# Charger.net
KiCad netlist of a schematic drawn in Altium Designer
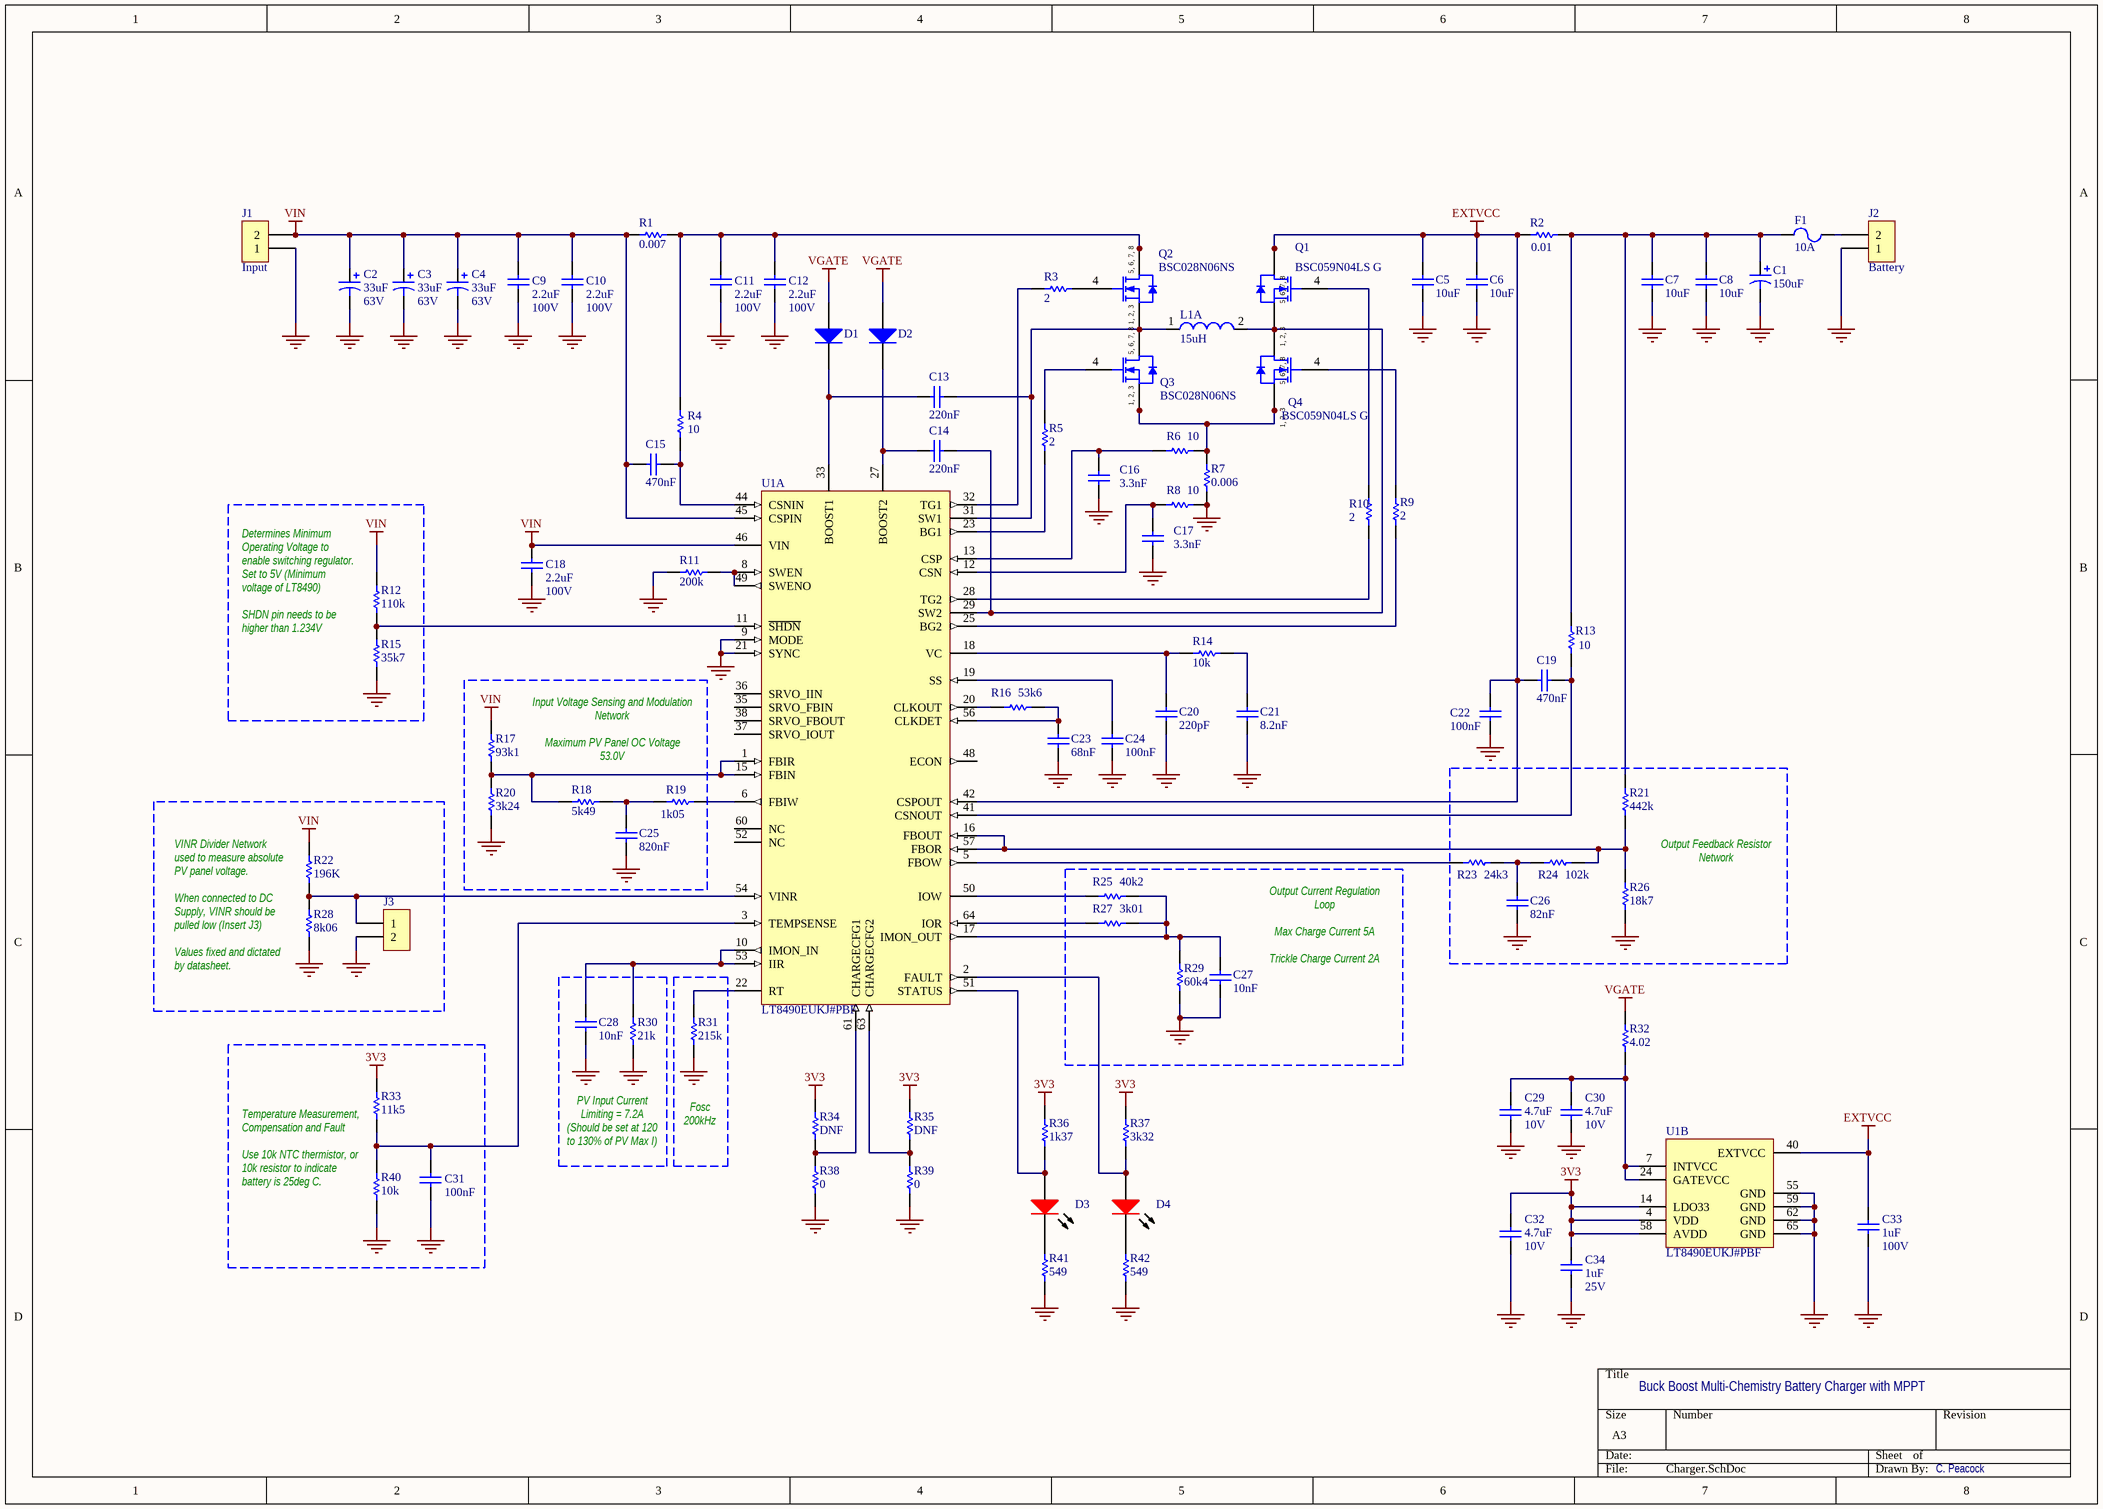
[diagram p0: Charger.SchDoc]

(export (version "E")
  (design (tool "Eeschema 10.0.6"))
  (components
    (comp (ref "C1")
      (value "150uF")
      (footprint "PCB-h7n8m0mive84y4pjomrj-1")
      (description "Capacitor Alum Elec, 150uf, 20%, 50v, Capacitor Alum Elec, 150uf, 20%, 50v, Smd, Full Reel")
      (libsource (lib "CommunityVault") (part "CMP-38bcf3ec736fe77b-2"))
    )
    (comp (ref "C2")
      (value "33uF")
      (footprint "PCB-9g04u1co75526zy4kkrl-1")
      (description "Cap Aluminum Lytic 33uF 63V 20% (8 X 10.2mm) SMD 250mA 2000h 105C Automotive T/R")
      (fields
        (field (name "MANUFACTURER PART NUMBER") "EEEFK1J330P")
        (field (name "VOLTAGE RATING (DC)") "63V")
      )
      (libsource (lib "CommunityVault") (part "CMP-7693bfcb6deba954-1"))
    )
    (comp (ref "C3")
      (value "33uF")
      (footprint "PCB-9g04u1co75526zy4kkrl-1")
      (description "Cap Aluminum Lytic 33uF 63V 20% (8 X 10.2mm) SMD 250mA 2000h 105C Automotive T/R")
      (fields
        (field (name "MANUFACTURER PART NUMBER") "EEEFK1J330P")
        (field (name "VOLTAGE RATING (DC)") "63V")
      )
      (libsource (lib "CommunityVault") (part "CMP-7693bfcb6deba954-1"))
    )
    (comp (ref "C4")
      (value "33uF")
      (footprint "PCB-9g04u1co75526zy4kkrl-1")
      (description "Cap Aluminum Lytic 33uF 63V 20% (8 X 10.2mm) SMD 250mA 2000h 105C Automotive T/R")
      (fields
        (field (name "MANUFACTURER PART NUMBER") "EEEFK1J330P")
        (field (name "VOLTAGE RATING (DC)") "63V")
      )
      (libsource (lib "CommunityVault") (part "CMP-7693bfcb6deba954-1"))
    )
    (comp (ref "C5")
      (value "10uF")
      (footprint "PCB-41pvis4jpu9wge287x0a-1")
      (description "1210 10 uF 35 V ±10% Tolerance X7R SMT Multilayer Ceramic Capacitor")
      (fields (field (name "MANUFACTURER PART NUMBER") "GRM32ER7YA106KA12L"))
      (libsource (lib "CommunityVault") (part "CMP-bd5774f6f82f6290-1"))
    )
    (comp (ref "C6")
      (value "10uF")
      (footprint "PCB-41pvis4jpu9wge287x0a-1")
      (description "1210 10 uF 35 V ±10% Tolerance X7R SMT Multilayer Ceramic Capacitor")
      (fields (field (name "MANUFACTURER PART NUMBER") "GRM32ER7YA106KA12L"))
      (libsource (lib "CommunityVault") (part "CMP-bd5774f6f82f6290-1"))
    )
    (comp (ref "C7")
      (value "10uF")
      (footprint "PCB-41pvis4jpu9wge287x0a-1")
      (description "1210 10 uF 35 V ±10% Tolerance X7R SMT Multilayer Ceramic Capacitor")
      (fields (field (name "MANUFACTURER PART NUMBER") "GRM32ER7YA106KA12L"))
      (libsource (lib "CommunityVault") (part "CMP-bd5774f6f82f6290-1"))
    )
    (comp (ref "C8")
      (value "10uF")
      (footprint "PCB-41pvis4jpu9wge287x0a-1")
      (description "1210 10 uF 35 V ±10% Tolerance X7R SMT Multilayer Ceramic Capacitor")
      (fields (field (name "MANUFACTURER PART NUMBER") "GRM32ER7YA106KA12L"))
      (libsource (lib "CommunityVault") (part "CMP-bd5774f6f82f6290-1"))
    )
    (comp (ref "C9")
      (value "2.2uF")
      (footprint "CAPC3225X279X50NL20T25")
      (description "Cap Ceramic 2.2uF 100V X7R 10% SMD 1210 125C Embossed T/R")
      (fields
        (field (name "VOLTAGE RATING (DC)") "100V")
        (field (name "MANUFACTURER PART NUMBER") "12101C225KAT2A")
      )
      (libsource (lib "CommunityVault") (part "CMP-2511202-3"))
    )
    (comp (ref "C10")
      (value "2.2uF")
      (footprint "CAPC3225X279X50NL20T25")
      (description "Cap Ceramic 2.2uF 100V X7R 10% SMD 1210 125C Embossed T/R")
      (fields
        (field (name "VOLTAGE RATING (DC)") "100V")
        (field (name "MANUFACTURER PART NUMBER") "12101C225KAT2A")
      )
      (libsource (lib "CommunityVault") (part "CMP-2511202-3"))
    )
    (comp (ref "C11")
      (value "2.2uF")
      (footprint "CAPC3225X279X50NL20T25")
      (description "Cap Ceramic 2.2uF 100V X7R 10% SMD 1210 125C Embossed T/R")
      (fields
        (field (name "VOLTAGE RATING (DC)") "100V")
        (field (name "MANUFACTURER PART NUMBER") "12101C225KAT2A")
      )
      (libsource (lib "CommunityVault") (part "CMP-2511202-3"))
    )
    (comp (ref "C12")
      (value "2.2uF")
      (footprint "CAPC3225X279X50NL20T25")
      (description "Cap Ceramic 2.2uF 100V X7R 10% SMD 1210 125C Embossed T/R")
      (fields
        (field (name "VOLTAGE RATING (DC)") "100V")
        (field (name "MANUFACTURER PART NUMBER") "12101C225KAT2A")
      )
      (libsource (lib "CommunityVault") (part "CMP-2511202-3"))
    )
    (comp (ref "C13")
      (value "220nF")
      (footprint "CAPC2013X140X50ML20T25")
      (description "Multilayer Ceramic Capacitors MLCC - SMD/SMT 50volts .22uF 5% X7R 7inch reel")
      (fields (field (name "MANUFACTURER PART NUMBER") "08055C224JAT2A"))
      (libsource (lib "CommunityVault") (part "CMP-3551434-3"))
    )
    (comp (ref "C14")
      (value "220nF")
      (footprint "CAPC2013X140X50ML20T25")
      (description "Multilayer Ceramic Capacitors MLCC - SMD/SMT 50volts .22uF 5% X7R 7inch reel")
      (fields (field (name "MANUFACTURER PART NUMBER") "08055C224JAT2A"))
      (libsource (lib "CommunityVault") (part "CMP-3551434-3"))
    )
    (comp (ref "C15")
      (value "470nF")
      (footprint "CAPC2013X140X50ML20T25")
      (description "Multilayer Ceramic Capacitors MLCC - SMD/SMT .47uF 50v 20% Tol.")
      (fields (field (name "MANUFACTURER PART NUMBER") "08055C474JAT2A"))
      (libsource (lib "CommunityVault") (part "CMP-3555014-4"))
    )
    (comp (ref "C16")
      (value "3.3nF")
      (footprint "CAPC2013X94X50ML20T25")
      (description "CAP CER 3300PF 50V 5% X7R 0805")
      (fields (field (name "MANUFACTURER PART NUMBER") "08055C332JAT2A"))
      (libsource (lib "CommunityVault") (part "CMP-173641-3"))
    )
    (comp (ref "C17")
      (value "3.3nF")
      (footprint "CAPC2013X94X50ML20T25")
      (description "CAP CER 3300PF 50V 5% X7R 0805")
      (fields (field (name "MANUFACTURER PART NUMBER") "08055C332JAT2A"))
      (libsource (lib "CommunityVault") (part "CMP-173641-3"))
    )
    (comp (ref "C18")
      (value "2.2uF")
      (footprint "CAPC3225X279X50NL20T25")
      (description "Cap Ceramic 2.2uF 100V X7R 10% SMD 1210 125C Embossed T/R")
      (fields
        (field (name "VOLTAGE RATING (DC)") "100V")
        (field (name "MANUFACTURER PART NUMBER") "12101C225KAT2A")
      )
      (libsource (lib "CommunityVault") (part "CMP-2511202-3"))
    )
    (comp (ref "C19")
      (value "470nF")
      (footprint "CAPC2013X140X50ML20T25")
      (description "Multilayer Ceramic Capacitors MLCC - SMD/SMT .47uF 50v 20% Tol.")
      (fields (field (name "MANUFACTURER PART NUMBER") "08055C474JAT2A"))
      (libsource (lib "CommunityVault") (part "CMP-3555014-4"))
    )
    (comp (ref "C20")
      (value "220pF")
      (footprint "CAPC2013X94X50ML20T25")
      (description "CAP CER 220PF 50V 5% X7R 0805")
      (fields (field (name "MANUFACTURER PART NUMBER") "08055C221JAT2A"))
      (libsource (lib "CommunityVault") (part "CMP-173636-3"))
    )
    (comp (ref "C21")
      (value "8.2nF")
      (footprint "CAPC2013X94X50ML20T25")
      (description "CAP CER 8200PF 50V 5% X7R 0805")
      (fields (field (name "MANUFACTURER PART NUMBER") "08055C822JAT2A"))
      (libsource (lib "CommunityVault") (part "CMP-173647-3"))
    )
    (comp (ref "C22")
      (value "100nF")
      (footprint "CAPC2013X140X50ML20T25")
      (description "Capacitor; Ceramic; Cap 0.1 uF; Tol 5%; Vol-Rtg 50 VDC; SMT; 0805; X7R; Tape & Reel")
      (fields (field (name "MANUFACTURER PART NUMBER") "08055C104JAT2A"))
      (libsource (lib "CommunityVault") (part "CMP-54a29ee556ae8b65-2"))
    )
    (comp (ref "C23")
      (value "68nF")
      (footprint "CAPC2013X94X50ML20T25")
      (description "CAP CER 0.068UF 50V 5% X7R 0805")
      (fields (field (name "MANUFACTURER PART NUMBER") "08055C683JAT2A"))
      (libsource (lib "CommunityVault") (part "CMP-174430-3"))
    )
    (comp (ref "C24")
      (value "100nF")
      (footprint "CAPC2013X140X50ML20T25")
      (description "Capacitor; Ceramic; Cap 0.1 uF; Tol 5%; Vol-Rtg 50 VDC; SMT; 0805; X7R; Tape & Reel")
      (fields (field (name "MANUFACTURER PART NUMBER") "08055C104JAT2A"))
      (libsource (lib "CommunityVault") (part "CMP-54a29ee556ae8b65-2"))
    )
    (comp (ref "C25")
      (value "820nF")
      (footprint "CAPC2013X95X45NL10T25")
      (description "Multilayer Ceramic Capacitors MLCC - SMD/SMT 0.82uF 25Volts X7R 0.1")
      (fields (field (name "MANUFACTURER PART NUMBER") "GRM219R71E824KA88D"))
      (libsource (lib "CommunityVault") (part "CAP-2"))
    )
    (comp (ref "C26")
      (value "82nF")
      (footprint "CAPC2013X94X50ML20T25")
      (description "CAP CER 0.082UF 50V 5% X7R 0805")
      (fields (field (name "MANUFACTURER PART NUMBER") "08055C823JAT2A"))
      (libsource (lib "CommunityVault") (part "CMP-174432-3"))
    )
    (comp (ref "C27")
      (value "10nF")
      (footprint "CAPC2013X94X50ML20T25")
      (description "cap smd 0805")
      (fields (field (name "MANUFACTURER PART NUMBER") "08055C103JAT2A"))
      (libsource (lib "CommunityVault") (part "CMP-16466678-4"))
    )
    (comp (ref "C28")
      (value "10nF")
      (footprint "CAPC2013X94X50ML20T25")
      (description "CAP CER 10NF 50V 5% X7R 0805")
      (fields (field (name "MANUFACTURER PART NUMBER") "08055C103JAT2A"))
      (libsource (lib "CommunityVault") (part "CMP-16466678-5"))
    )
    (comp (ref "C29")
      (value "4.7uF")
      (footprint "CAPC2013X140X50ML20T25")
      (description "CAP CER 4.7UF 10V 10% X5R 0805")
      (fields
        (field (name "VOLTAGE RATING (DC)") "10V")
        (field (name "MANUFACTURER PART NUMBER") "0805ZD475KAT2A")
      )
      (libsource (lib "CommunityVault") (part "CMP-126761-3"))
    )
    (comp (ref "C30")
      (value "4.7uF")
      (footprint "CAPC2013X140X50ML20T25")
      (description "CAP CER 4.7UF 10V 10% X5R 0805")
      (fields
        (field (name "VOLTAGE RATING (DC)") "10V")
        (field (name "MANUFACTURER PART NUMBER") "0805ZD475KAT2A")
      )
      (libsource (lib "CommunityVault") (part "CMP-126761-3"))
    )
    (comp (ref "C31")
      (value "100nF")
      (footprint "CAPC2013X140X50ML20T25")
      (description "Capacitor; Ceramic; Cap 0.1 uF; Tol 5%; Vol-Rtg 50 VDC; SMT; 0805; X7R; Tape & Reel")
      (fields (field (name "MANUFACTURER PART NUMBER") "08055C104JAT2A"))
      (libsource (lib "CommunityVault") (part "CMP-54a29ee556ae8b65-2"))
    )
    (comp (ref "C32")
      (value "4.7uF")
      (footprint "CAPC2013X140X50ML20T25")
      (description "CAP CER 4.7UF 10V 10% X5R 0805")
      (fields
        (field (name "VOLTAGE RATING (DC)") "10V")
        (field (name "MANUFACTURER PART NUMBER") "0805ZD475KAT2A")
      )
      (libsource (lib "CommunityVault") (part "CMP-126761-3"))
    )
    (comp (ref "C33")
      (value "1uF")
      (footprint "CAPC3225X279X50ML20T25")
      (description "CAP CER 1UF 100V 10% X7R 1210")
      (fields
        (field (name "VOLTAGE RATING (DC)") "100V")
        (field (name "MANUFACTURER PART NUMBER") "12101C105KAT2A")
      )
      (libsource (lib "CommunityVault") (part "CMP-127163-3"))
    )
    (comp (ref "C34")
      (value "1uF")
      (footprint "CAPC2013X140X50ML20T25")
      (description "CAP CER 1UF 25V 10% X5R 0805")
      (fields
        (field (name "MANUFACTURER PART NUMBER") "08053D105KAT2A")
        (field (name "VOLTAGE RATING (DC)") "25V")
      )
      (libsource (lib "CommunityVault") (part "CAP-2"))
    )
    (comp (ref "D1")
      (value "1N4148WS")
      (footprint "FSC-1N4148WS-SOD-323-2")
      (description "DIODE GEN PURP 75V 150MA SOD323F")
      (libsource (lib "CommunityVault") (part "D_K1A2-2"))
    )
    (comp (ref "D2")
      (value "1N4148WS")
      (footprint "FSC-1N4148WS-SOD-323-2")
      (description "DIODE GEN PURP 75V 150MA SOD323F")
      (libsource (lib "CommunityVault") (part "D_K1A2-2"))
    )
    (comp (ref "D3")
      (value "Lite-On LTST-C170KRKT")
      (footprint "PCB-5ta9mte2am12bu12jwvi-1")
      (description "Red 2 x 1.25 x 1.1 mm 130° Water Clear 54 mcd 2 V LED Surface Mount")
      (fields (field (name "MANUFACTURER PART NUMBER") "LTST-C170KRKT"))
      (libsource (lib "CommunityVault") (part "CMP-1544870-4"))
    )
    (comp (ref "D4")
      (value "Lite-On LTST-C170KRKT")
      (footprint "PCB-5ta9mte2am12bu12jwvi-1")
      (description "Red 2 x 1.25 x 1.1 mm 130° Water Clear 54 mcd 2 V LED Surface Mount")
      (fields (field (name "MANUFACTURER PART NUMBER") "LTST-C170KRKT"))
      (libsource (lib "CommunityVault") (part "CMP-1544870-4"))
    )
    (comp (ref "F1")
      (value "10A")
      (footprint "PCB-nlucop3bvobg45y57dd7-1")
      (description "154 Series Fast-Acting 125 V 10 A OMNI-BLOK® Surface Mount Fuse & Holder")
      (fields (field (name "MANUFACTURER PART NUMBER") "0154010.DR"))
      (libsource (lib "CommunityVault") (part "CMP-254385-4"))
    )
    (comp (ref "J1")
      (value "Input")
      (footprint "PCB-aknpg75yzj2hq04tmkjt-1")
      (fields (field (name "MANUFACTURER PART NUMBER") "1757242"))
      (libsource (lib "") (part "SYM-0680cf8a1162d947-1_1"))
    )
    (comp (ref "J2")
      (value "Battery")
      (footprint "PCB-aknpg75yzj2hq04tmkjt-1")
      (fields (field (name "MANUFACTURER PART NUMBER") "1757242"))
      (libsource (lib "FavoritesLibrary") (part "SYM-0680cf8a1162d947-1"))
    )
    (comp (ref "J3")
      (value "Molex 90120-0762")
      (footprint "PCB-zbro1p3mqdrs1lkjydms-1")
      (description "2.54mm (.100\") Pitch C-Grid III Header, Single Row, Vertical, 1 Circuits, Gold (Au) Plating")
      (fields (field (name "MANUFACTURER PART NUMBER") "90120-0762"))
      (libsource (lib "CommunityVault") (part "SYM-8fae46aeaafe5069-1"))
    )
    (comp (ref "L1")
      (value "15uH")
      (footprint "WE-HCF 2818")
      (description "SMD High Current Inductor WE-HCF, L=15µH")
      (libsource (lib "CommunityVault") (part "PAS-IND-INDUCTOR-3"))
    )
    (comp (ref "Q1")
      (value "BSC059N04LS G")
      (footprint "INF-PG-TDSON-8-1_V")
      (libsource (lib "CommunityVault") (part "INF-NEMOS-SSSGDDDD-8"))
    )
    (comp (ref "Q2")
      (value "BSC028N06NS")
      (footprint "INF-PG-TDSON-8-1_V")
      (description "N-Channel OptiMOS Power-Transistor, 60 V VDS, 100 A ID, -55 to 150 degC, PG-TDSON-8-1, Reel, Green")
      (libsource (lib "CommunityVault") (part "INF-NEMOS-SSSGDDDD-8"))
    )
    (comp (ref "Q3")
      (value "BSC028N06NS")
      (footprint "INF-PG-TDSON-8-1_V")
      (description "N-Channel OptiMOS Power-Transistor, 60 V VDS, 100 A ID, -55 to 150 degC, PG-TDSON-8-1, Reel, Green")
      (libsource (lib "CommunityVault") (part "INF-NEMOS-SSSGDDDD-8"))
    )
    (comp (ref "Q4")
      (value "BSC059N04LS G")
      (footprint "INF-PG-TDSON-8-1_V")
      (libsource (lib "CommunityVault") (part "CMP-840507-3"))
    )
    (comp (ref "R1")
      (value "0.007")
      (footprint "Resistor")
      (description "Res Metal Alloy 2512 7m Ohm 1% 2W ±75ppm/°C Molded SMD Embossed Carrier T/R")
      (fields (field (name "MANUFACTURER PART NUMBER") "ERJ-MS4HF7M0U"))
      (libsource (lib "CommunityVault") (part "SYM-3140fbc44d5aee87-1"))
    )
    (comp (ref "R2")
      (value "0.01")
      (footprint "Resistor")
      (description "Res Metal Alloy 2512 10m Ohm 1% 2W ±75ppm/°C Molded SMD Embossed Carrier T/R")
      (fields (field (name "MANUFACTURER PART NUMBER") "ERJ-MS4HF10MU"))
      (libsource (lib "FavoritesLibrary") (part "SYM-3ffef57a43e1e039-1"))
    )
    (comp (ref "R3")
      (value "2")
      (footprint "RESC2013X60X35NL10T20")
      (description "RC Series 0805 0.125 W 2 Ohms 1% ±100 ppm/°C SMT Thick Film Chip Resistor")
      (fields (field (name "MANUFACTURER PART NUMBER") "RC0805FR-072RL"))
      (libsource (lib "CommunityVault") (part "SYM-0849c1512bc3d78e-1"))
    )
    (comp (ref "R4")
      (value "10")
      (footprint "RESC2013X60X35ML10T20")
      (description "RC Series 0805 0.125 W 10 Ohms 1% ±100 ppm/°C SMT Thick Film Chip Resistor")
      (fields (field (name "MANUFACTURER PART NUMBER") "RC0805FR-0710RL"))
      (libsource (lib "CommunityVault") (part "SYM-0281c9fbc26fdd46-1"))
    )
    (comp (ref "R5")
      (value "2")
      (footprint "RESC2013X60X35ML10T20")
      (description "RC Series 0805 0.125 W 2 Ohms 1% ±100 ppm/°C SMT Thick Film Chip Resistor")
      (fields (field (name "MANUFACTURER PART NUMBER") "RC0805FR-072RL"))
      (libsource (lib "CommunityVault") (part "SYM-0849c1512bc3d78e-1"))
    )
    (comp (ref "R6")
      (value "10")
      (footprint "RESC2013X60X35ML10T20")
      (description "RC Series 0805 0.125 W 10 Ohms 1% ±100 ppm/°C SMT Thick Film Chip Resistor")
      (fields (field (name "MANUFACTURER PART NUMBER") "RC0805FR-0710RL"))
      (libsource (lib "CommunityVault") (part "SYM-0281c9fbc26fdd46-1"))
    )
    (comp (ref "R7")
      (value "0.006")
      (footprint "Resistor")
      (description "Res Metal Alloy 2512 6m Ohm 1% 3W ±75ppm/°C Molded SMD Embossed Carrier T/R")
      (fields (field (name "MANUFACTURER PART NUMBER") "ERJ-MS4HF6M0U"))
      (libsource (lib "CommunityVault") (part "CMP-23c4e9405fd9fc03-1"))
    )
    (comp (ref "R8")
      (value "10")
      (footprint "RESC2013X60X35ML10T20")
      (description "RC Series 0805 0.125 W 10 Ohms 1% ±100 ppm/°C SMT Thick Film Chip Resistor")
      (fields (field (name "MANUFACTURER PART NUMBER") "RC0805FR-0710RL"))
      (libsource (lib "CommunityVault") (part "SYM-0281c9fbc26fdd46-1"))
    )
    (comp (ref "R9")
      (value "2")
      (footprint "RESC2013X60X35ML10T20")
      (description "RC Series 0805 0.125 W 2 Ohms 1% ±100 ppm/°C SMT Thick Film Chip Resistor")
      (fields (field (name "MANUFACTURER PART NUMBER") "RC0805FR-072RL"))
      (libsource (lib "CommunityVault") (part "SYM-0849c1512bc3d78e-1"))
    )
    (comp (ref "R10")
      (value "2")
      (footprint "RESC2013X60X35ML10T20")
      (description "RC Series 0805 0.125 W 2 Ohms 1% ±100 ppm/°C SMT Thick Film Chip Resistor")
      (fields (field (name "MANUFACTURER PART NUMBER") "RC0805FR-072RL"))
      (libsource (lib "CommunityVault") (part "SYM-0849c1512bc3d78e-1"))
    )
    (comp (ref "R11")
      (value "200k")
      (footprint "RESC2013X60X35ML10T20")
      (description "RC Series 0805 0.125 W 200 kOhms 1% ±100 ppm/°C SMT Thick Film Chip Resistor")
      (fields (field (name "MANUFACTURER PART NUMBER") "RC0805FR-07200KL"))
      (libsource (lib "CommunityVault") (part "CMP-e4272f597d573be0-1"))
    )
    (comp (ref "R12")
      (value "110k")
      (footprint "RESC2013X60X35ML10T20")
      (description "RC Series 0805 0.125 W 110 kOhms 1% ±100 ppm/°C SMT Thick Film Chip Resistor")
      (fields (field (name "MANUFACTURER PART NUMBER") "RC0805FR-07110KL"))
      (libsource (lib "CommunityVault") (part "SYM-38f6f2b2e11ce731-1"))
    )
    (comp (ref "R13")
      (value "10")
      (footprint "RESC2013X60X35ML10T20")
      (description "RC Series 0805 0.125 W 10 Ohms 1% ±100 ppm/°C SMT Thick Film Chip Resistor")
      (fields (field (name "MANUFACTURER PART NUMBER") "RC0805FR-0710RL"))
      (libsource (lib "CommunityVault") (part "SYM-0281c9fbc26fdd46-1"))
    )
    (comp (ref "R14")
      (value "10k")
      (footprint "RESC2013X60X35ML10T20")
      (description "RC Series 0805 0.125 W 10 kOhms 1% ±100 ppm/°C SMT Thick Film Chip Resistor")
      (fields (field (name "MANUFACTURER PART NUMBER") "RC0805FR-0710KL"))
      (libsource (lib "") (part "RES-2_1"))
    )
    (comp (ref "R15")
      (value "35k7")
      (footprint "RESC2013X60X35ML10T20")
      (description "RC Series 0805 0.125 W 35.7 kOhms 1% ±100 ppm/°C SMT Thick Film Chip Resistor")
      (fields (field (name "MANUFACTURER PART NUMBER") "RC0805FR-0735K7L"))
      (libsource (lib "CommunityVault") (part "RES-2"))
    )
    (comp (ref "R16")
      (value "53k6")
      (footprint "RESC2013X60X35ML10T20")
      (description "RC Series 0805 0.125 W 53.6 kOhms 1% ±100 ppm/°C SMT Thick Film Chip Resistor")
      (fields (field (name "MANUFACTURER PART NUMBER") "RC0805FR-0753K6L"))
      (libsource (lib "CommunityVault") (part "RES-2"))
    )
    (comp (ref "R17")
      (value "93k1")
      (footprint "RESC2013X60X35ML10T20")
      (description "RC Series 0805 0.125 W 93.1 kOhms 1% ±100 ppm/°C SMT Thick Film Chip Resistor")
      (fields (field (name "MANUFACTURER PART NUMBER") "RC0805FR-0793K1L"))
      (libsource (lib "CommunityVault") (part "CMP-1854487-3"))
    )
    (comp (ref "R18")
      (value "5k49")
      (footprint "RESC2013X60X35ML10T20")
      (description "RC Series 0805 0.125 W 5.49 kOhms 1% ±100 ppm/°C SMT Thick Film Chip Resistor")
      (fields (field (name "MANUFACTURER PART NUMBER") "RC0805FR-075K49L"))
      (libsource (lib "CommunityVault") (part "RES-2"))
    )
    (comp (ref "R19")
      (value "1k05")
      (footprint "RESC2013X60X35ML10T20")
      (description "RC Series 0805 0.125 W 1.05 kOhms 1% ±100 ppm/°C SMT Thick Film Chip Resistor")
      (fields (field (name "MANUFACTURER PART NUMBER") "RC0805FR-071K05L"))
      (libsource (lib "CommunityVault") (part "SYM-b5997e3e74036a5e-1"))
    )
    (comp (ref "R20")
      (value "3k24")
      (footprint "RESC2013X60X35ML10T20")
      (description "RC Series 0805 0.125 W 3.24 kOhms 1% ±100 ppm/°C SMT Thick Film Chip Resistor")
      (fields (field (name "MANUFACTURER PART NUMBER") "RC0805FR-073K24L"))
      (libsource (lib "CommunityVault") (part "CMP-1854678-3"))
    )
    (comp (ref "R21")
      (value "442k")
      (footprint "RESC2013X60X35ML10T20")
      (description "RC Series 0805 0.125 W 442 kOhms 1% ±100 ppm/°C SMT Thick Film Chip Resistor")
      (fields (field (name "MANUFACTURER PART NUMBER") "RC0805FR-07442KL"))
      (libsource (lib "CommunityVault") (part "RES-2"))
    )
    (comp (ref "R22")
      (value "196K")
      (footprint "RESC2013X60X35ML10T20")
      (description "RC Series 0805 0.125 W 196 kOhms 1% ±100 ppm/°C SMT Thick Film Chip Resistor")
      (fields (field (name "MANUFACTURER PART NUMBER") "RC0805FR-07196KL"))
      (libsource (lib "CommunityVault") (part "CMP-97215c7414f848e6-2"))
    )
    (comp (ref "R23")
      (value "24k3")
      (footprint "RESC2013X60X35ML10T20")
      (description "RC Series 0805 0.125 W 24.3 kOhms 1% ±100 ppm/°C SMT Thick Film Chip Resistor")
      (fields (field (name "MANUFACTURER PART NUMBER") "RC0805FR-0724K3L"))
      (libsource (lib "CommunityVault") (part "RES-2"))
    )
    (comp (ref "R24")
      (value "102k")
      (footprint "RESC2013X60X35ML10T20")
      (description "RC Series 0805 0.125 W 102 kOhms 1% ±100 ppm/°C SMT Thick Film Chip Resistor")
      (fields (field (name "MANUFACTURER PART NUMBER") "RC0805FR-07102KL"))
      (libsource (lib "CommunityVault") (part "RES-2"))
    )
    (comp (ref "R25")
      (value "40k2")
      (footprint "RESC2013X60X35ML10T20")
      (description "RC Series 0805 0.125 W 40.2 kOhms 1% ±100 ppm/°C SMT Thick Film Chip Resistor")
      (fields (field (name "MANUFACTURER PART NUMBER") "RC0805FR-0740K2L"))
      (libsource (lib "CommunityVault") (part "CMP-a88663d3e8667741-1"))
    )
    (comp (ref "R26")
      (value "18k7")
      (footprint "RESC2013X60X35ML10T20")
      (description "RC Series 0805 0.125 W 18.7 kOhms 1% ±100 ppm/°C SMT Thick Film Chip Resistor")
      (fields (field (name "MANUFACTURER PART NUMBER") "RC0805FR-0718K7L"))
      (libsource (lib "CommunityVault") (part "SYM-c8620311b81c17a5-1"))
    )
    (comp (ref "R27")
      (value "3k01")
      (footprint "RESC2013X60X35ML10T20")
      (description "RC Series 0805 0.125 W 3.01 kOhms 1% ±100 ppm/°C SMT Thick Film Chip Resistor")
      (fields (field (name "MANUFACTURER PART NUMBER") "RC0805FR-073K01L"))
      (libsource (lib "CommunityVault") (part "CMP-7c68b5716a47a3af-1"))
    )
    (comp (ref "R28")
      (value "8k06")
      (footprint "RESC2013X60X35ML10T20")
      (description "RC Series 0805 0.125 W 8.06 kOhms 1% ±100 ppm/°C SMT Thick Film Chip Resistor")
      (fields (field (name "MANUFACTURER PART NUMBER") "RC0805FR-078K06L"))
      (libsource (lib "CommunityVault") (part "CMP-f925303c7afe26e2-2"))
    )
    (comp (ref "R29")
      (value "60k4")
      (footprint "RESC2013X60X35ML10T20")
      (description "RC Series 0805 0.125 W 60.4 kOhms 1% ±100 ppm/°C SMT Thick Film Chip Resistor")
      (fields (field (name "MANUFACTURER PART NUMBER") "RC0805FR-0760K4L"))
      (libsource (lib "CommunityVault") (part "CMP-bfd776c8b5e36010-1"))
    )
    (comp (ref "R30")
      (value "21k")
      (footprint "RESC2013X60X35ML10T20")
      (description "RC Series 0805 0.125 W 21 kOhms 1% ±100 ppm/°C SMT Thick Film Chip Resistor")
      (fields (field (name "MANUFACTURER PART NUMBER") "RC0805FR-0721KL"))
      (libsource (lib "CommunityVault") (part "CMP-1875654-3"))
    )
    (comp (ref "R31")
      (value "215k")
      (footprint "RESC2013X60X35ML10T20")
      (description "RC Series 0805 0.125 W 215 kOhms 1% ±100 ppm/°C SMT Thick Film Chip Resistor")
      (fields (field (name "MANUFACTURER PART NUMBER") "RC0805FR-07215KL"))
      (libsource (lib "CommunityVault") (part "CMP-5dec96b9cda1822b-1"))
    )
    (comp (ref "R32")
      (value "4.02")
      (footprint "RESC2013X60X35ML10T20")
      (description "RC Series 0805 0.125 W 4.02 Ohms 1% ±100 ppm/°C SMT Thick Film Chip Resistor")
      (fields (field (name "MANUFACTURER PART NUMBER") "RC0805FR-074R02L"))
      (libsource (lib "CommunityVault") (part "RES-2"))
    )
    (comp (ref "R33")
      (value "11k5")
      (footprint "RESC2013X60X35ML10T20")
      (description "RC Series 0805 0.125 W 11.5k Ohm 1% ±100 ppm/°C SMT Thick Film Chip Resistor")
      (fields (field (name "MANUFACTURER PART NUMBER") "RC0805FR-0711K5L"))
      (libsource (lib "CommunityVault") (part "SYM-8094498c85275f53-1"))
    )
    (comp (ref "R34")
      (value "DNF")
      (footprint "RESC2013X60X35ML10T20")
      (description "Res Thick Film 0805 0 Ohm Molded SMD Paper T/R")
      (libsource (lib "CommunityVault") (part "CMP-1875921-6"))
    )
    (comp (ref "R35")
      (value "DNF")
      (footprint "RESC2013X60X35ML10T20")
      (description "Res Thick Film 0805 0 Ohm Molded SMD Paper T/R")
      (libsource (lib "CommunityVault") (part "CMP-1875921-6"))
    )
    (comp (ref "R36")
      (value "1k37")
      (footprint "RESC2013X60X35ML10T20")
      (description "RC Series 0805 0.125 W 1.37 kOhms 1% ±100 ppm/°C SMT Thick Film Chip Resistor")
      (fields (field (name "MANUFACTURER PART NUMBER") "RC0805FR-071K37L"))
      (libsource (lib "CommunityVault") (part "RES-2"))
    )
    (comp (ref "R37")
      (value "3k32")
      (footprint "RESC2013X60X35ML10T20")
      (description "RC Series 0805 0.125 W 3.32 kOhms 1% ±100 ppm/°C SMT Thick Film Chip Resistor")
      (fields (field (name "MANUFACTURER PART NUMBER") "RC0805FR-073K32L"))
      (libsource (lib "CommunityVault") (part "CMP-5d85960ed7bd8242-1"))
    )
    (comp (ref "R38")
      (value "0")
      (footprint "RESC2013X60X35ML10T20")
      (description "Res Thick Film 0805 0 Ohm Molded SMD Paper T/R")
      (fields (field (name "MANUFACTURER PART NUMBER") "RC0805FR-070RL"))
      (libsource (lib "CommunityVault") (part "SYM-f3d13a5618eb2c16-1"))
    )
    (comp (ref "R39")
      (value "0")
      (footprint "RESC2013X60X35ML10T20")
      (description "Res Thick Film 0805 0 Ohm Molded SMD Paper T/R")
      (fields (field (name "MANUFACTURER PART NUMBER") "RC0805FR-070RL"))
      (libsource (lib "CommunityVault") (part "CMP-1875921-8"))
    )
    (comp (ref "R40")
      (value "10k")
      (footprint "RESC2013X60X35ML10T20")
      (description "RC Series 0805 0.125 W 10 kOhms 1% ±100 ppm/°C SMT Thick Film Chip Resistor")
      (fields (field (name "MANUFACTURER PART NUMBER") "RC0805FR-0710KL"))
      (libsource (lib "") (part "RES-2_1"))
    )
    (comp (ref "R41")
      (value "549")
      (footprint "RESC2013X60X35ML10T20")
      (description "RC Series 0805 0.125 W 549 Ohms 1% ±100 ppm/°C SMT Thick Film Chip Resistor")
      (fields (field (name "MANUFACTURER PART NUMBER") "RC0805FR-07549RL"))
      (libsource (lib "CommunityVault") (part "RES-2"))
    )
    (comp (ref "R42")
      (value "549")
      (footprint "RESC2013X60X35ML10T20")
      (description "RC Series 0805 0.125 W 549 Ohms 1% ±100 ppm/°C SMT Thick Film Chip Resistor")
      (fields (field (name "MANUFACTURER PART NUMBER") "RC0805FR-07549RL"))
      (libsource (lib "CommunityVault") (part "RES-2"))
    )
    (comp (ref "U1")
      (value "LT8490EUKJ#PBF")
      (footprint "LT-UKJ64(58)_V")
      (libsource (lib "") (part "CMP-20381226-2_1"))
    )
  )
  (nets
    (net (code "1") (name "3V3") (class "Default")
      (node (ref "C32") (pin "2") (pinfunction "2_2") (pintype "passive"))
      (node (ref "C34") (pin "2") (pinfunction "2_2") (pintype "passive"))
      (node (ref "R33") (pin "2") (pinfunction "2_2") (pintype "passive"))
      (node (ref "R34") (pin "2") (pinfunction "2_2") (pintype "passive"))
      (node (ref "R35") (pin "2") (pinfunction "2_2") (pintype "passive"))
      (node (ref "R36") (pin "2") (pinfunction "2_2") (pintype "passive"))
      (node (ref "R37") (pin "2") (pinfunction "2_2") (pintype "passive"))
      (node (ref "U1") (pin "14") (pinfunction "LDO33_14") (pintype "power_in"))
      (node (ref "U1") (pin "4") (pinfunction "VDD_4") (pintype "power_in"))
      (node (ref "U1") (pin "58") (pinfunction "AVDD_58") (pintype "power_in"))
    )
    (net (code "2") (name "EXTVCC") (class "Default")
      (node (ref "C19") (pin "1") (pinfunction "1_1") (pintype "passive"))
      (node (ref "C22") (pin "2") (pinfunction "2_2") (pintype "passive"))
      (node (ref "C33") (pin "2") (pinfunction "2_2") (pintype "passive"))
      (node (ref "C5") (pin "2") (pinfunction "2_2") (pintype "passive"))
      (node (ref "C6") (pin "2") (pinfunction "2_2") (pintype "passive"))
      (node (ref "Q1") (pin "5") (pinfunction "DRAIN_5") (pintype "passive"))
      (node (ref "Q1") (pin "6") (pinfunction "DRAIN_6") (pintype "passive"))
      (node (ref "Q1") (pin "7") (pinfunction "DRAIN_7") (pintype "passive"))
      (node (ref "Q1") (pin "8") (pinfunction "DRAIN_8") (pintype "passive"))
      (node (ref "R2") (pin "1") (pinfunction "1_1") (pintype "passive"))
      (node (ref "U1") (pin "40") (pinfunction "EXTVCC_40") (pintype "power_in"))
      (node (ref "U1") (pin "42") (pinfunction "CSPOUT_42") (pintype "input"))
    )
    (net (code "3") (name "GND") (class "Default")
      (node (ref "C1") (pin "2") (pinfunction "2_2") (pintype "passive"))
      (node (ref "C10") (pin "1") (pinfunction "1_1") (pintype "passive"))
      (node (ref "C11") (pin "1") (pinfunction "1_1") (pintype "passive"))
      (node (ref "C12") (pin "1") (pinfunction "1_1") (pintype "passive"))
      (node (ref "C16") (pin "1") (pinfunction "1_1") (pintype "passive"))
      (node (ref "C17") (pin "1") (pinfunction "1_1") (pintype "passive"))
      (node (ref "C18") (pin "1") (pinfunction "1_1") (pintype "passive"))
      (node (ref "C2") (pin "2") (pinfunction "2_2") (pintype "passive"))
      (node (ref "C20") (pin "1") (pinfunction "1_1") (pintype "passive"))
      (node (ref "C21") (pin "1") (pinfunction "1_1") (pintype "passive"))
      (node (ref "C22") (pin "1") (pinfunction "1_1") (pintype "passive"))
      (node (ref "C23") (pin "1") (pinfunction "1_1") (pintype "passive"))
      (node (ref "C24") (pin "1") (pinfunction "1_1") (pintype "passive"))
      (node (ref "C25") (pin "1") (pinfunction "1_1") (pintype "passive"))
      (node (ref "C26") (pin "1") (pinfunction "1_1") (pintype "passive"))
      (node (ref "C27") (pin "1") (pinfunction "1_1") (pintype "passive"))
      (node (ref "C28") (pin "1") (pinfunction "1_1") (pintype "passive"))
      (node (ref "C29") (pin "1") (pinfunction "1_1") (pintype "passive"))
      (node (ref "C3") (pin "2") (pinfunction "2_2") (pintype "passive"))
      (node (ref "C30") (pin "1") (pinfunction "1_1") (pintype "passive"))
      (node (ref "C31") (pin "1") (pinfunction "1_1") (pintype "passive"))
      (node (ref "C32") (pin "1") (pinfunction "1_1") (pintype "passive"))
      (node (ref "C33") (pin "1") (pinfunction "1_1") (pintype "passive"))
      (node (ref "C34") (pin "1") (pinfunction "1_1") (pintype "passive"))
      (node (ref "C4") (pin "2") (pinfunction "2_2") (pintype "passive"))
      (node (ref "C5") (pin "1") (pinfunction "1_1") (pintype "passive"))
      (node (ref "C6") (pin "1") (pinfunction "1_1") (pintype "passive"))
      (node (ref "C7") (pin "1") (pinfunction "1_1") (pintype "passive"))
      (node (ref "C8") (pin "1") (pinfunction "1_1") (pintype "passive"))
      (node (ref "C9") (pin "1") (pinfunction "1_1") (pintype "passive"))
      (node (ref "J1") (pin "1") (pinfunction "1_1") (pintype "passive"))
      (node (ref "J2") (pin "1") (pinfunction "1_1") (pintype "passive"))
      (node (ref "J3") (pin "2") (pinfunction "2_2") (pintype "passive"))
      (node (ref "R11") (pin "1") (pinfunction "1_1") (pintype "passive"))
      (node (ref "R15") (pin "1") (pinfunction "1_1") (pintype "passive"))
      (node (ref "R20") (pin "1") (pinfunction "1_1") (pintype "passive"))
      (node (ref "R26") (pin "1") (pinfunction "1_1") (pintype "passive"))
      (node (ref "R28") (pin "1") (pinfunction "1_1") (pintype "passive"))
      (node (ref "R29") (pin "1") (pinfunction "1_1") (pintype "passive"))
      (node (ref "R30") (pin "1") (pinfunction "1_1") (pintype "passive"))
      (node (ref "R31") (pin "1") (pinfunction "1_1") (pintype "passive"))
      (node (ref "R38") (pin "1") (pinfunction "1_1") (pintype "passive"))
      (node (ref "R39") (pin "1") (pinfunction "1_1") (pintype "passive"))
      (node (ref "R40") (pin "1") (pinfunction "1_1") (pintype "passive"))
      (node (ref "R41") (pin "1") (pinfunction "1_1") (pintype "passive"))
      (node (ref "R42") (pin "1") (pinfunction "1_1") (pintype "passive"))
      (node (ref "R7") (pin "1") (pinfunction "1_1") (pintype "passive"))
      (node (ref "R8") (pin "1") (pinfunction "1_1") (pintype "passive"))
      (node (ref "U1") (pin "21") (pinfunction "SYNC_21") (pintype "input"))
      (node (ref "U1") (pin "55") (pinfunction "GND_55") (pintype "power_in"))
      (node (ref "U1") (pin "59") (pinfunction "GND_59") (pintype "power_in"))
      (node (ref "U1") (pin "62") (pinfunction "GND_62") (pintype "power_in"))
      (node (ref "U1") (pin "65") (pinfunction "GND_65") (pintype "power_in"))
      (node (ref "U1") (pin "9") (pinfunction "MODE_9") (pintype "input"))
    )
    (net (code "4") (name "Net-(C1-Pad1)") (class "Default")
      (node (ref "C1") (pin "1") (pinfunction "1_1") (pintype "passive"))
      (node (ref "C7") (pin "2") (pinfunction "2_2") (pintype "passive"))
      (node (ref "C8") (pin "2") (pinfunction "2_2") (pintype "passive"))
      (node (ref "F1") (pin "1") (pinfunction "1_1") (pintype "passive"))
      (node (ref "R13") (pin "2") (pinfunction "2_2") (pintype "passive"))
      (node (ref "R2") (pin "2") (pinfunction "2_2") (pintype "passive"))
      (node (ref "R21") (pin "2") (pinfunction "2_2") (pintype "passive"))
    )
    (net (code "5") (name "Net-(C11-Pad2)") (class "Default")
      (node (ref "C11") (pin "2") (pinfunction "2_2") (pintype "passive"))
      (node (ref "C12") (pin "2") (pinfunction "2_2") (pintype "passive"))
      (node (ref "Q2") (pin "5") (pinfunction "DRAIN_5") (pintype "passive"))
      (node (ref "Q2") (pin "6") (pinfunction "DRAIN_6") (pintype "passive"))
      (node (ref "Q2") (pin "7") (pinfunction "DRAIN_7") (pintype "passive"))
      (node (ref "Q2") (pin "8") (pinfunction "DRAIN_8") (pintype "passive"))
      (node (ref "R1") (pin "2") (pinfunction "2_2") (pintype "passive"))
      (node (ref "R4") (pin "2") (pinfunction "2_2") (pintype "passive"))
    )
    (net (code "6") (name "Net-(C21-Pad2)") (class "Default")
      (node (ref "C21") (pin "2") (pinfunction "2_2") (pintype "passive"))
      (node (ref "R14") (pin "1") (pinfunction "1_1") (pintype "passive"))
    )
    (net (code "7") (name "Net-(C25-Pad2)") (class "Default")
      (node (ref "C25") (pin "2") (pinfunction "2_2") (pintype "passive"))
      (node (ref "R18") (pin "2") (pinfunction "2_2") (pintype "passive"))
      (node (ref "R19") (pin "1") (pinfunction "1_1") (pintype "passive"))
    )
    (net (code "8") (name "Net-(C26-Pad2)") (class "Default")
      (node (ref "C26") (pin "2") (pinfunction "2_2") (pintype "passive"))
      (node (ref "R23") (pin "2") (pinfunction "2_2") (pintype "passive"))
      (node (ref "R24") (pin "1") (pinfunction "1_1") (pintype "passive"))
    )
    (net (code "9") (name "Net-(D1-K)") (class "Default")
      (node (ref "C13") (pin "1") (pinfunction "1_1") (pintype "passive"))
      (node (ref "D1") (pin "1") (pinfunction "K_1") (pintype "passive"))
      (node (ref "U1") (pin "33") (pinfunction "BOOST1_33") (pintype "passive"))
    )
    (net (code "10") (name "Net-(D2-K)") (class "Default")
      (node (ref "C14") (pin "1") (pinfunction "1_1") (pintype "passive"))
      (node (ref "D2") (pin "1") (pinfunction "K_1") (pintype "passive"))
      (node (ref "U1") (pin "27") (pinfunction "BOOST2_27") (pintype "passive"))
    )
    (net (code "11") (name "Net-(D3-A)") (class "Default")
      (node (ref "D3") (pin "2") (pinfunction "A_2") (pintype "passive"))
      (node (ref "R36") (pin "1") (pinfunction "1_1") (pintype "passive"))
      (node (ref "U1") (pin "51") (pinfunction "STATUS_51") (pintype "output"))
    )
    (net (code "12") (name "Net-(D3-K)") (class "Default")
      (node (ref "D3") (pin "1") (pinfunction "K_1") (pintype "passive"))
      (node (ref "R41") (pin "2") (pinfunction "2_2") (pintype "passive"))
    )
    (net (code "13") (name "Net-(D4-A)") (class "Default")
      (node (ref "D4") (pin "2") (pinfunction "A_2") (pintype "passive"))
      (node (ref "R37") (pin "1") (pinfunction "1_1") (pintype "passive"))
      (node (ref "U1") (pin "2") (pinfunction "FAULT_2") (pintype "output"))
    )
    (net (code "14") (name "Net-(D4-K)") (class "Default")
      (node (ref "D4") (pin "1") (pinfunction "K_1") (pintype "passive"))
      (node (ref "R42") (pin "2") (pinfunction "2_2") (pintype "passive"))
    )
    (net (code "15") (name "Net-(F1-Pad2)") (class "Default")
      (node (ref "F1") (pin "2") (pinfunction "2_2") (pintype "passive"))
      (node (ref "J2") (pin "2") (pinfunction "2_2") (pintype "passive"))
    )
    (net (code "16") (name "Net-(Q1-GATE)") (class "Default")
      (node (ref "Q1") (pin "4") (pinfunction "GATE_4") (pintype "passive"))
      (node (ref "R10") (pin "2") (pinfunction "2_2") (pintype "passive"))
    )
    (net (code "17") (name "Net-(Q2-GATE)") (class "Default")
      (node (ref "Q2") (pin "4") (pinfunction "GATE_4") (pintype "passive"))
      (node (ref "R3") (pin "2") (pinfunction "2_2") (pintype "passive"))
    )
    (net (code "18") (name "Net-(Q3-GATE)") (class "Default")
      (node (ref "Q3") (pin "4") (pinfunction "GATE_4") (pintype "passive"))
      (node (ref "R5") (pin "2") (pinfunction "2_2") (pintype "passive"))
    )
    (net (code "19") (name "Net-(Q3-SOURCE-Pad1)") (class "Default")
      (node (ref "Q3") (pin "1") (pinfunction "SOURCE_1") (pintype "passive"))
      (node (ref "Q3") (pin "2") (pinfunction "SOURCE_2") (pintype "passive"))
      (node (ref "Q3") (pin "3") (pinfunction "SOURCE_3") (pintype "passive"))
      (node (ref "Q4") (pin "1") (pinfunction "SOURCE_1") (pintype "passive"))
      (node (ref "Q4") (pin "2") (pinfunction "SOURCE_2") (pintype "passive"))
      (node (ref "Q4") (pin "3") (pinfunction "SOURCE_3") (pintype "passive"))
      (node (ref "R6") (pin "1") (pinfunction "1_1") (pintype "passive"))
      (node (ref "R7") (pin "2") (pinfunction "2_2") (pintype "passive"))
    )
    (net (code "20") (name "Net-(Q4-GATE)") (class "Default")
      (node (ref "Q4") (pin "4") (pinfunction "GATE_4") (pintype "passive"))
      (node (ref "R9") (pin "2") (pinfunction "2_2") (pintype "passive"))
    )
    (net (code "21") (name "Net-(U1A-BG1)") (class "Default")
      (node (ref "R5") (pin "1") (pinfunction "1_1") (pintype "passive"))
      (node (ref "U1") (pin "23") (pinfunction "BG1_23") (pintype "output"))
    )
    (net (code "22") (name "Net-(U1A-BG2)") (class "Default")
      (node (ref "R9") (pin "1") (pinfunction "1_1") (pintype "passive"))
      (node (ref "U1") (pin "25") (pinfunction "BG2_25") (pintype "output"))
    )
    (net (code "23") (name "Net-(U1A-CHARGECFG1)") (class "Default")
      (node (ref "R34") (pin "1") (pinfunction "1_1") (pintype "passive"))
      (node (ref "R38") (pin "2") (pinfunction "2_2") (pintype "passive"))
      (node (ref "U1") (pin "61") (pinfunction "CHARGECFG1_61") (pintype "input"))
    )
    (net (code "24") (name "Net-(U1A-CHARGECFG2)") (class "Default")
      (node (ref "R35") (pin "1") (pinfunction "1_1") (pintype "passive"))
      (node (ref "R39") (pin "2") (pinfunction "2_2") (pintype "passive"))
      (node (ref "U1") (pin "63") (pinfunction "CHARGECFG2_63") (pintype "input"))
    )
    (net (code "25") (name "Net-(U1A-CLKDET)") (class "Default")
      (node (ref "C23") (pin "2") (pinfunction "2_2") (pintype "passive"))
      (node (ref "R16") (pin "2") (pinfunction "2_2") (pintype "passive"))
      (node (ref "U1") (pin "56") (pinfunction "CLKDET_56") (pintype "input"))
    )
    (net (code "26") (name "Net-(U1A-CLKOUT)") (class "Default")
      (node (ref "R16") (pin "1") (pinfunction "1_1") (pintype "passive"))
      (node (ref "U1") (pin "20") (pinfunction "CLKOUT_20") (pintype "output"))
    )
    (net (code "27") (name "Net-(U1A-CSN)") (class "Default")
      (node (ref "C17") (pin "2") (pinfunction "2_2") (pintype "passive"))
      (node (ref "R8") (pin "2") (pinfunction "2_2") (pintype "passive"))
      (node (ref "U1") (pin "12") (pinfunction "CSN_12") (pintype "input"))
    )
    (net (code "28") (name "Net-(U1A-CSNIN)") (class "Default")
      (node (ref "C15") (pin "2") (pinfunction "2_2") (pintype "passive"))
      (node (ref "R4") (pin "1") (pinfunction "1_1") (pintype "passive"))
      (node (ref "U1") (pin "44") (pinfunction "CSNIN_44") (pintype "input"))
    )
    (net (code "29") (name "Net-(U1A-CSNOUT)") (class "Default")
      (node (ref "C19") (pin "2") (pinfunction "2_2") (pintype "passive"))
      (node (ref "R13") (pin "1") (pinfunction "1_1") (pintype "passive"))
      (node (ref "U1") (pin "41") (pinfunction "CSNOUT_41") (pintype "input"))
    )
    (net (code "30") (name "Net-(U1A-CSP)") (class "Default")
      (node (ref "C16") (pin "2") (pinfunction "2_2") (pintype "passive"))
      (node (ref "R6") (pin "2") (pinfunction "2_2") (pintype "passive"))
      (node (ref "U1") (pin "13") (pinfunction "CSP_13") (pintype "input"))
    )
    (net (code "31") (name "Net-(U1A-FBIN)") (class "Default")
      (node (ref "R17") (pin "1") (pinfunction "1_1") (pintype "passive"))
      (node (ref "R18") (pin "1") (pinfunction "1_1") (pintype "passive"))
      (node (ref "R20") (pin "2") (pinfunction "2_2") (pintype "passive"))
      (node (ref "U1") (pin "1") (pinfunction "FBIR_1") (pintype "input"))
      (node (ref "U1") (pin "15") (pinfunction "FBIN_15") (pintype "input"))
    )
    (net (code "32") (name "Net-(U1A-FBIW)") (class "Default")
      (node (ref "R19") (pin "2") (pinfunction "2_2") (pintype "passive"))
      (node (ref "U1") (pin "6") (pinfunction "FBIW_6") (pintype "output"))
    )
    (net (code "33") (name "Net-(U1A-FBOR)") (class "Default")
      (node (ref "R21") (pin "1") (pinfunction "1_1") (pintype "passive"))
      (node (ref "R24") (pin "2") (pinfunction "2_2") (pintype "passive"))
      (node (ref "R26") (pin "2") (pinfunction "2_2") (pintype "passive"))
      (node (ref "U1") (pin "16") (pinfunction "FBOUT_16") (pintype "input"))
      (node (ref "U1") (pin "57") (pinfunction "FBOR_57") (pintype "input"))
    )
    (net (code "34") (name "Net-(U1A-FBOW)") (class "Default")
      (node (ref "R23") (pin "1") (pinfunction "1_1") (pintype "passive"))
      (node (ref "U1") (pin "5") (pinfunction "FBOW_5") (pintype "output"))
    )
    (net (code "35") (name "Net-(U1A-IIR)") (class "Default")
      (node (ref "C28") (pin "2") (pinfunction "2_2") (pintype "passive"))
      (node (ref "R30") (pin "2") (pinfunction "2_2") (pintype "passive"))
      (node (ref "U1") (pin "10") (pinfunction "IMON_IN_10") (pintype "output"))
      (node (ref "U1") (pin "53") (pinfunction "IIR_53") (pintype "input"))
    )
    (net (code "36") (name "Net-(U1A-IMON_OUT)") (class "Default")
      (node (ref "C27") (pin "2") (pinfunction "2_2") (pintype "passive"))
      (node (ref "R25") (pin "2") (pinfunction "2_2") (pintype "passive"))
      (node (ref "R27") (pin "2") (pinfunction "2_2") (pintype "passive"))
      (node (ref "R29") (pin "2") (pinfunction "2_2") (pintype "passive"))
      (node (ref "U1") (pin "17") (pinfunction "IMON_OUT_17") (pintype "output"))
    )
    (net (code "37") (name "Net-(U1A-IOR)") (class "Default")
      (node (ref "R27") (pin "1") (pinfunction "1_1") (pintype "passive"))
      (node (ref "U1") (pin "64") (pinfunction "IOR_64") (pintype "input"))
    )
    (net (code "38") (name "Net-(U1A-IOW)") (class "Default")
      (node (ref "R25") (pin "1") (pinfunction "1_1") (pintype "passive"))
      (node (ref "U1") (pin "50") (pinfunction "IOW_50") (pintype "tri_state"))
    )
    (net (code "39") (name "Net-(U1A-RT)") (class "Default")
      (node (ref "R31") (pin "2") (pinfunction "2_2") (pintype "passive"))
      (node (ref "U1") (pin "22") (pinfunction "RT_22") (pintype "passive"))
    )
    (net (code "40") (name "Net-(U1A-SS)") (class "Default")
      (node (ref "C24") (pin "2") (pinfunction "2_2") (pintype "passive"))
      (node (ref "U1") (pin "19") (pinfunction "SS_19") (pintype "input"))
    )
    (net (code "41") (name "Net-(U1A-SW1)") (class "Default")
      (node (ref "C13") (pin "2") (pinfunction "2_2") (pintype "passive"))
      (node (ref "L1") (pin "1") (pinfunction "1_1") (pintype "passive"))
      (node (ref "Q2") (pin "1") (pinfunction "SOURCE_1") (pintype "passive"))
      (node (ref "Q2") (pin "2") (pinfunction "SOURCE_2") (pintype "passive"))
      (node (ref "Q2") (pin "3") (pinfunction "SOURCE_3") (pintype "passive"))
      (node (ref "Q3") (pin "5") (pinfunction "DRAIN_5") (pintype "passive"))
      (node (ref "Q3") (pin "6") (pinfunction "DRAIN_6") (pintype "passive"))
      (node (ref "Q3") (pin "7") (pinfunction "DRAIN_7") (pintype "passive"))
      (node (ref "Q3") (pin "8") (pinfunction "DRAIN_8") (pintype "passive"))
      (node (ref "U1") (pin "31") (pinfunction "SW1_31") (pintype "passive"))
    )
    (net (code "42") (name "Net-(U1A-SW2)") (class "Default")
      (node (ref "C14") (pin "2") (pinfunction "2_2") (pintype "passive"))
      (node (ref "L1") (pin "2") (pinfunction "2_2") (pintype "passive"))
      (node (ref "Q1") (pin "1") (pinfunction "SOURCE_1") (pintype "passive"))
      (node (ref "Q1") (pin "2") (pinfunction "SOURCE_2") (pintype "passive"))
      (node (ref "Q1") (pin "3") (pinfunction "SOURCE_3") (pintype "passive"))
      (node (ref "Q4") (pin "5") (pinfunction "DRAIN_5") (pintype "passive"))
      (node (ref "Q4") (pin "6") (pinfunction "DRAIN_6") (pintype "passive"))
      (node (ref "Q4") (pin "7") (pinfunction "DRAIN_7") (pintype "passive"))
      (node (ref "Q4") (pin "8") (pinfunction "DRAIN_8") (pintype "passive"))
      (node (ref "U1") (pin "29") (pinfunction "SW2_29") (pintype "passive"))
    )
    (net (code "43") (name "Net-(U1A-SWEN)") (class "Default")
      (node (ref "R11") (pin "2") (pinfunction "2_2") (pintype "passive"))
      (node (ref "U1") (pin "49") (pinfunction "SWENO_49") (pintype "output"))
      (node (ref "U1") (pin "8") (pinfunction "SWEN_8") (pintype "input"))
    )
    (net (code "44") (name "Net-(U1A-TEMPSENSE)") (class "Default")
      (node (ref "C31") (pin "2") (pinfunction "2_2") (pintype "passive"))
      (node (ref "R33") (pin "1") (pinfunction "1_1") (pintype "passive"))
      (node (ref "R40") (pin "2") (pinfunction "2_2") (pintype "passive"))
      (node (ref "U1") (pin "3") (pinfunction "TEMPSENSE_3") (pintype "input"))
    )
    (net (code "45") (name "Net-(U1A-TG1)") (class "Default")
      (node (ref "R3") (pin "1") (pinfunction "1_1") (pintype "passive"))
      (node (ref "U1") (pin "32") (pinfunction "TG1_32") (pintype "output"))
    )
    (net (code "46") (name "Net-(U1A-TG2)") (class "Default")
      (node (ref "R10") (pin "1") (pinfunction "1_1") (pintype "passive"))
      (node (ref "U1") (pin "28") (pinfunction "TG2_28") (pintype "output"))
    )
    (net (code "47") (name "Net-(U1A-VC)") (class "Default")
      (node (ref "C20") (pin "2") (pinfunction "2_2") (pintype "passive"))
      (node (ref "R14") (pin "2") (pinfunction "2_2") (pintype "passive"))
      (node (ref "U1") (pin "18") (pinfunction "VC_18") (pintype "passive"))
    )
    (net (code "48") (name "Net-(U1A-VINR)") (class "Default")
      (node (ref "J3") (pin "1") (pinfunction "1_1") (pintype "passive"))
      (node (ref "R22") (pin "1") (pinfunction "1_1") (pintype "passive"))
      (node (ref "R28") (pin "2") (pinfunction "2_2") (pintype "passive"))
      (node (ref "U1") (pin "54") (pinfunction "VINR_54") (pintype "input"))
    )
    (net (code "49") (name "Net-(U1A-~{SHDN})") (class "Default")
      (node (ref "R12") (pin "1") (pinfunction "1_1") (pintype "passive"))
      (node (ref "R15") (pin "2") (pinfunction "2_2") (pintype "passive"))
      (node (ref "U1") (pin "11") (pinfunction "~{SHDN}_11") (pintype "input"))
    )
    (net (code "50") (name "Net-(U1B-GATEVCC)") (class "Default")
      (node (ref "C29") (pin "2") (pinfunction "2_2") (pintype "passive"))
      (node (ref "C30") (pin "2") (pinfunction "2_2") (pintype "passive"))
      (node (ref "R32") (pin "1") (pinfunction "1_1") (pintype "passive"))
      (node (ref "U1") (pin "24") (pinfunction "GATEVCC_24") (pintype "power_in"))
      (node (ref "U1") (pin "7") (pinfunction "INTVCC_7") (pintype "power_in"))
    )
    (net (code "51") (name "VGATE") (class "Default")
      (node (ref "D1") (pin "2") (pinfunction "A_2") (pintype "passive"))
      (node (ref "D2") (pin "2") (pinfunction "A_2") (pintype "passive"))
      (node (ref "R32") (pin "2") (pinfunction "2_2") (pintype "passive"))
    )
    (net (code "52") (name "VIN") (class "Default")
      (node (ref "C10") (pin "2") (pinfunction "2_2") (pintype "passive"))
      (node (ref "C15") (pin "1") (pinfunction "1_1") (pintype "passive"))
      (node (ref "C18") (pin "2") (pinfunction "2_2") (pintype "passive"))
      (node (ref "C2") (pin "1") (pinfunction "1_1") (pintype "passive"))
      (node (ref "C3") (pin "1") (pinfunction "1_1") (pintype "passive"))
      (node (ref "C4") (pin "1") (pinfunction "1_1") (pintype "passive"))
      (node (ref "C9") (pin "2") (pinfunction "2_2") (pintype "passive"))
      (node (ref "J1") (pin "2") (pinfunction "2_2") (pintype "passive"))
      (node (ref "R1") (pin "1") (pinfunction "1_1") (pintype "passive"))
      (node (ref "R12") (pin "2") (pinfunction "2_2") (pintype "passive"))
      (node (ref "R17") (pin "2") (pinfunction "2_2") (pintype "passive"))
      (node (ref "R22") (pin "2") (pinfunction "2_2") (pintype "passive"))
      (node (ref "U1") (pin "45") (pinfunction "CSPIN_45") (pintype "input"))
      (node (ref "U1") (pin "46") (pinfunction "VIN_46") (pintype "power_in"))
    )
    (net (code "53") (name "unconnected-(U1A-ECON-Pad48)") (class "Default")
      (node (ref "U1") (pin "48") (pinfunction "ECON_48") (pintype "output"))
    )
    (net (code "54") (name "unconnected-(U1A-NC-Pad52)") (class "Default")
      (node (ref "U1") (pin "52") (pinfunction "NC_52") (pintype "passive"))
    )
    (net (code "55") (name "unconnected-(U1A-NC-Pad60)") (class "Default")
      (node (ref "U1") (pin "60") (pinfunction "NC_60") (pintype "passive"))
    )
    (net (code "56") (name "unconnected-(U1A-SRVO_FBIN-Pad35)") (class "Default")
      (node (ref "U1") (pin "35") (pinfunction "SRVO_FBIN_35") (pintype "passive"))
    )
    (net (code "57") (name "unconnected-(U1A-SRVO_FBOUT-Pad38)") (class "Default")
      (node (ref "U1") (pin "38") (pinfunction "SRVO_FBOUT_38") (pintype "passive"))
    )
    (net (code "58") (name "unconnected-(U1A-SRVO_IIN-Pad36)") (class "Default")
      (node (ref "U1") (pin "36") (pinfunction "SRVO_IIN_36") (pintype "passive"))
    )
    (net (code "59") (name "unconnected-(U1A-SRVO_IOUT-Pad37)") (class "Default")
      (node (ref "U1") (pin "37") (pinfunction "SRVO_IOUT_37") (pintype "passive"))
    )
  )
)
